# amper.net
KiCad netlist of a schematic drawn in EAGLE
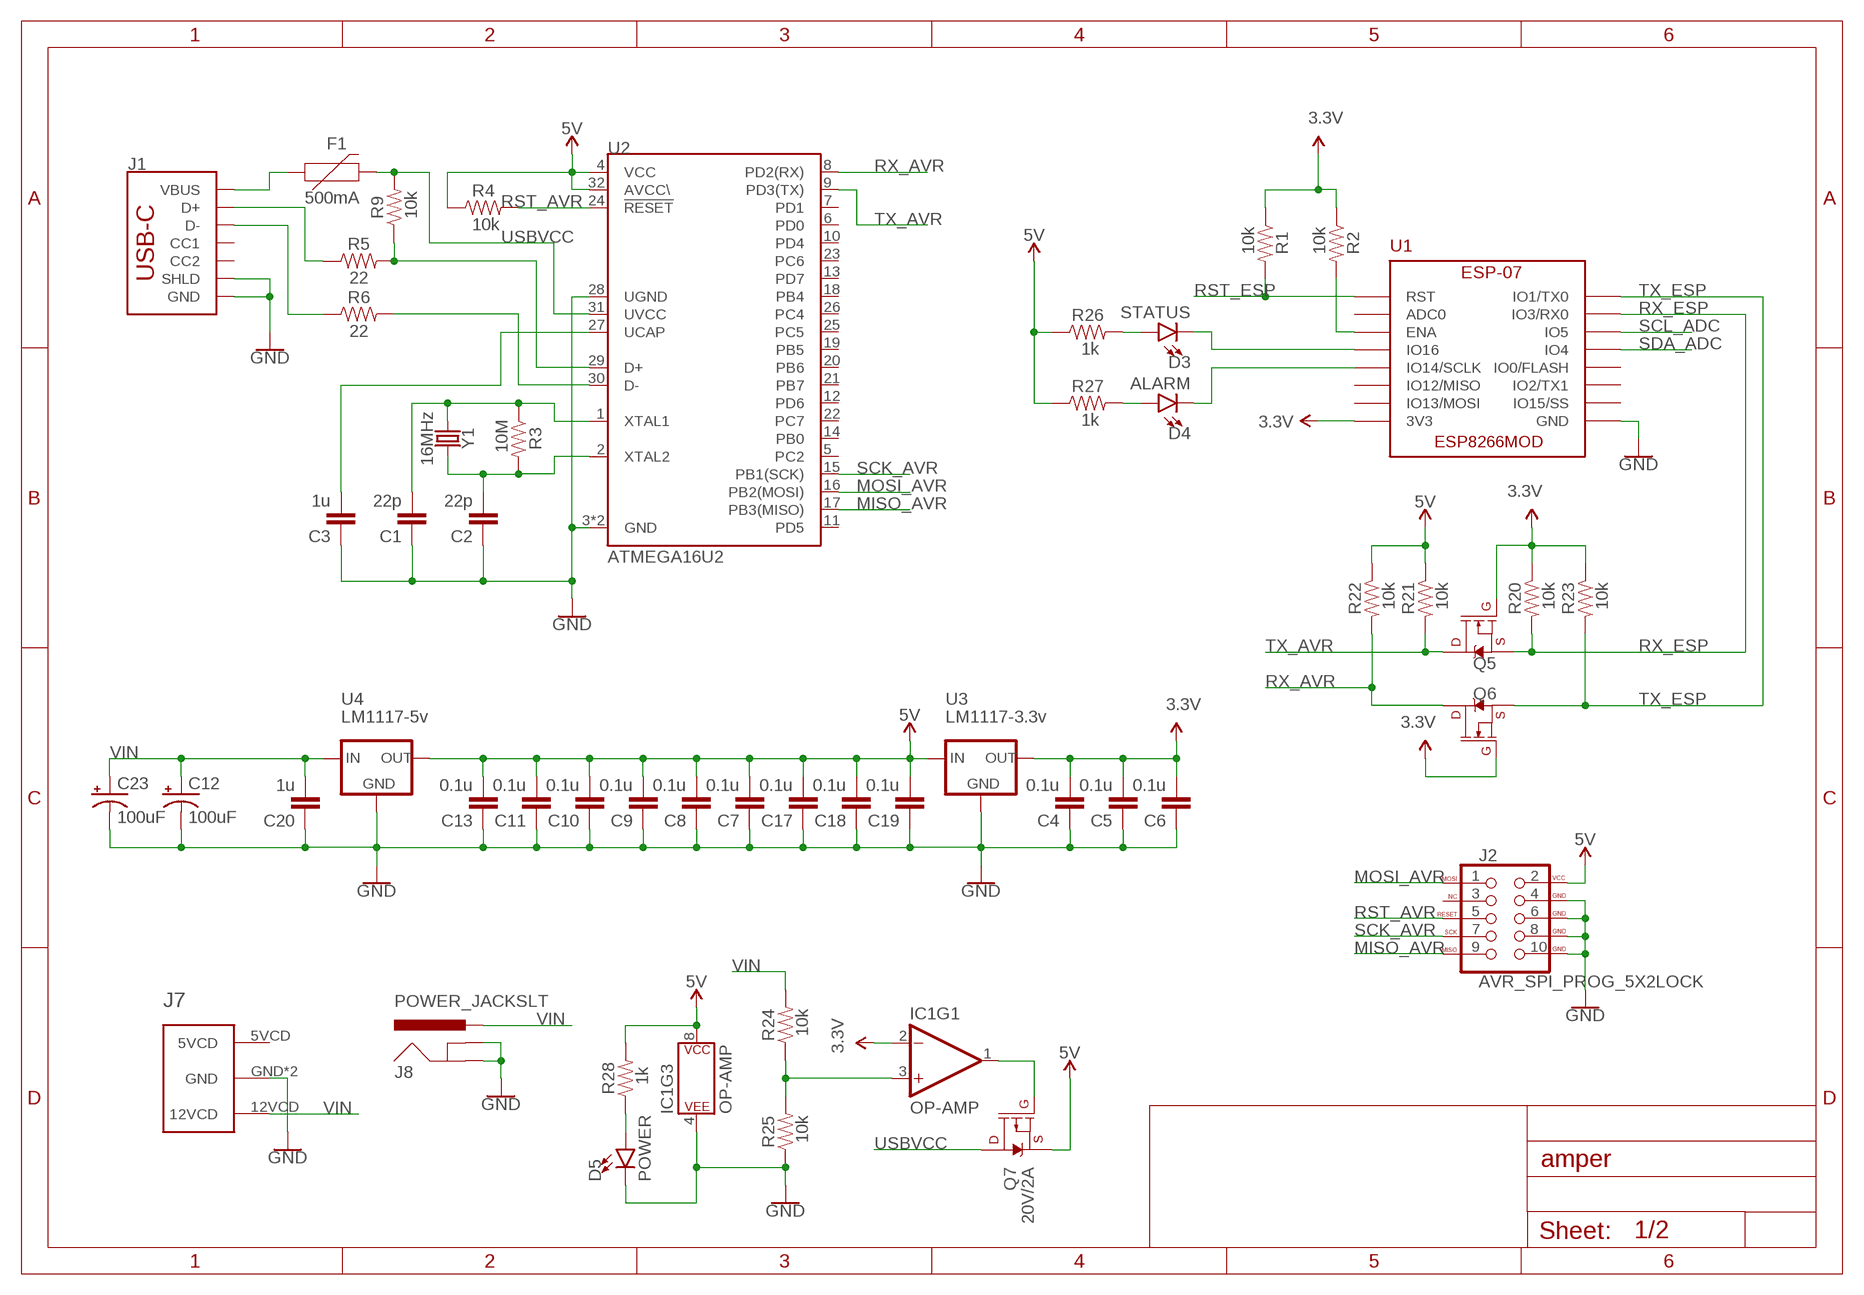
[diagram p0: schematic, sheet 1]
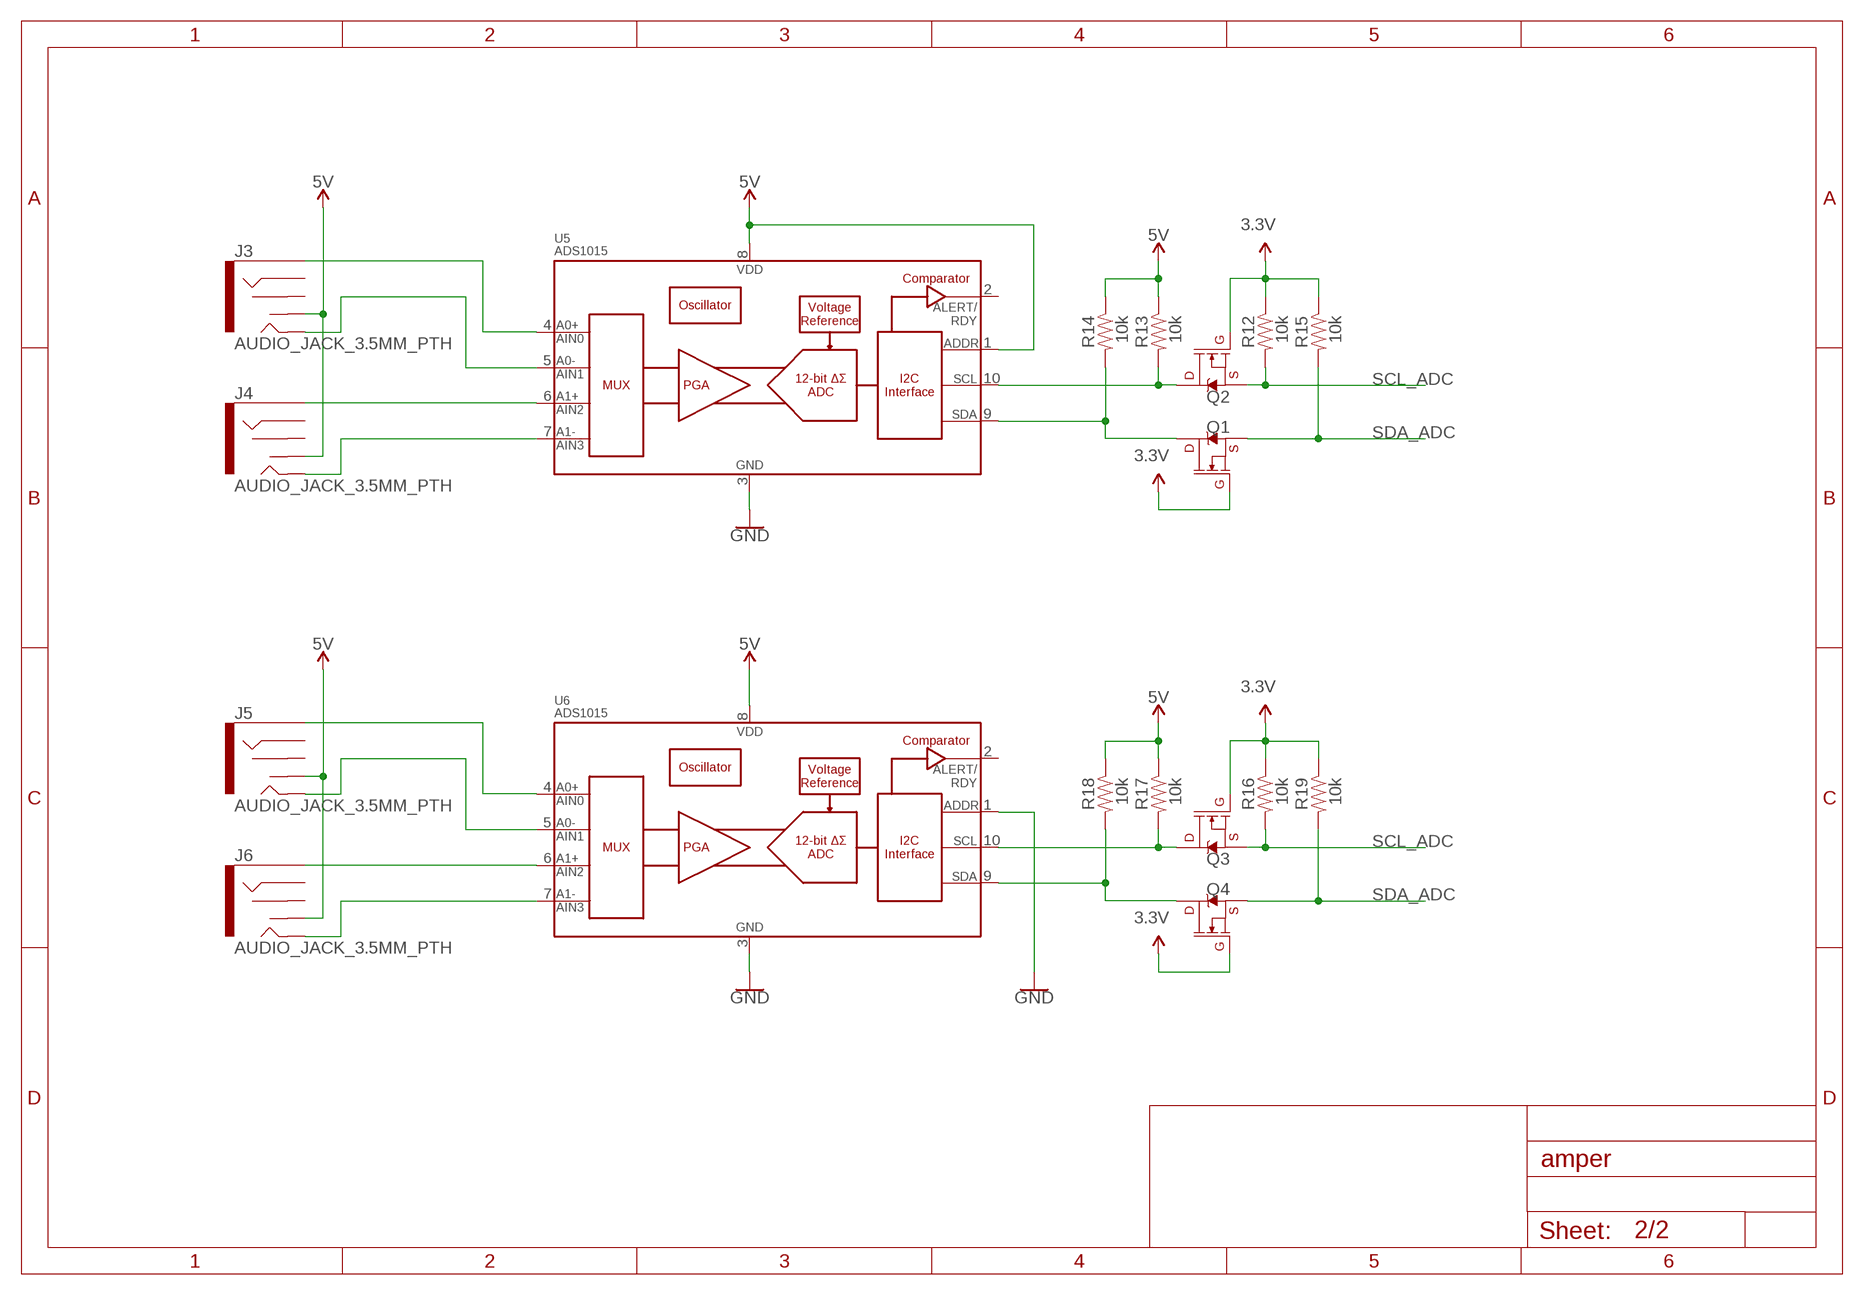
[diagram p1: schematic, sheet 2]

(export (version "E")
  (design (tool "Eeschema 10.0.6"))
  (components
    (comp (ref "J3")
      (value "AUDIO_JACK_3.5MM_PTH")
      (footprint "eagle-import:AUDIO-JACK")
      (libsource (lib "eagle-import") (part "AUDIO_JACK_3.5MM_PTH"))
    )
    (comp (ref "J4")
      (value "AUDIO_JACK_3.5MM_PTH")
      (footprint "eagle-import:AUDIO-JACK")
      (libsource (lib "eagle-import") (part "AUDIO_JACK_3.5MM_PTH"))
    )
    (comp (ref "J5")
      (value "AUDIO_JACK_3.5MM_PTH")
      (footprint "eagle-import:AUDIO-JACK")
      (libsource (lib "eagle-import") (part "AUDIO_JACK_3.5MM_PTH"))
    )
    (comp (ref "J6")
      (value "AUDIO_JACK_3.5MM_PTH")
      (footprint "eagle-import:AUDIO-JACK")
      (libsource (lib "eagle-import") (part "AUDIO_JACK_3.5MM_PTH"))
    )
    (comp (ref "Q1")
      (value "220mA/50V/3.5Ω")
      (footprint "eagle-import:SOT23-3")
      (libsource (lib "eagle-import") (part "MOSFET-NCH-BSS138"))
    )
    (comp (ref "Q2")
      (value "220mA/50V/3.5Ω")
      (footprint "eagle-import:SOT23-3")
      (libsource (lib "eagle-import") (part "MOSFET-NCH-BSS138"))
    )
    (comp (ref "Q3")
      (value "220mA/50V/3.5Ω")
      (footprint "eagle-import:SOT23-3")
      (libsource (lib "eagle-import") (part "MOSFET-NCH-BSS138"))
    )
    (comp (ref "Q4")
      (value "220mA/50V/3.5Ω")
      (footprint "eagle-import:SOT23-3")
      (libsource (lib "eagle-import") (part "MOSFET-NCH-BSS138"))
    )
    (comp (ref "R12")
      (value "10k")
      (footprint "eagle-import:0805")
      (libsource (lib "eagle-import") (part "RESISTOR0805"))
    )
    (comp (ref "R13")
      (value "10k")
      (footprint "eagle-import:0805")
      (libsource (lib "eagle-import") (part "RESISTOR0805"))
    )
    (comp (ref "R14")
      (value "10k")
      (footprint "eagle-import:0805")
      (libsource (lib "eagle-import") (part "RESISTOR0805"))
    )
    (comp (ref "R15")
      (value "10k")
      (footprint "eagle-import:0805")
      (libsource (lib "eagle-import") (part "RESISTOR0805"))
    )
    (comp (ref "R16")
      (value "10k")
      (footprint "eagle-import:0805")
      (libsource (lib "eagle-import") (part "RESISTOR0805"))
    )
    (comp (ref "R17")
      (value "10k")
      (footprint "eagle-import:0805")
      (libsource (lib "eagle-import") (part "RESISTOR0805"))
    )
    (comp (ref "R18")
      (value "10k")
      (footprint "eagle-import:0805")
      (libsource (lib "eagle-import") (part "RESISTOR0805"))
    )
    (comp (ref "R19")
      (value "10k")
      (footprint "eagle-import:0805")
      (libsource (lib "eagle-import") (part "RESISTOR0805"))
    )
    (comp (ref "U5")
      (value "ADS1015")
      (footprint "eagle-import:MSOP10")
      (libsource (lib "eagle-import") (part "ADS1015"))
    )
    (comp (ref "U6")
      (value "ADS1015")
      (footprint "eagle-import:MSOP10")
      (libsource (lib "eagle-import") (part "ADS1015"))
    )
    (comp (ref "C1")
      (value "22p")
      (footprint "eagle-import:0805")
      (libsource (lib "eagle-import") (part "CAP-0805"))
    )
    (comp (ref "C2")
      (value "22p")
      (footprint "eagle-import:0805")
      (libsource (lib "eagle-import") (part "CAP-0805"))
    )
    (comp (ref "C3")
      (value "1u")
      (footprint "eagle-import:0805")
      (libsource (lib "eagle-import") (part "CAP-0805"))
    )
    (comp (ref "C4")
      (value "0.1u")
      (footprint "eagle-import:0805")
      (libsource (lib "eagle-import") (part "CAP-0805"))
    )
    (comp (ref "C5")
      (value "0.1u")
      (footprint "eagle-import:0805")
      (libsource (lib "eagle-import") (part "CAP-0805"))
    )
    (comp (ref "C6")
      (value "0.1u")
      (footprint "eagle-import:0805")
      (libsource (lib "eagle-import") (part "CAP-0805"))
    )
    (comp (ref "C7")
      (value "0.1u")
      (footprint "eagle-import:0805")
      (libsource (lib "eagle-import") (part "CAP-0805"))
    )
    (comp (ref "C8")
      (value "0.1u")
      (footprint "eagle-import:0805")
      (libsource (lib "eagle-import") (part "CAP-0805"))
    )
    (comp (ref "C9")
      (value "0.1u")
      (footprint "eagle-import:0805")
      (libsource (lib "eagle-import") (part "CAP-0805"))
    )
    (comp (ref "C10")
      (value "0.1u")
      (footprint "eagle-import:0805")
      (libsource (lib "eagle-import") (part "CAP-0805"))
    )
    (comp (ref "C11")
      (value "0.1u")
      (footprint "eagle-import:0805")
      (libsource (lib "eagle-import") (part "CAP-0805"))
    )
    (comp (ref "C12")
      (value "100uF")
      (footprint "eagle-import:PANASONIC_D")
      (libsource (lib "eagle-import") (part "100UF-POLAR-25V-20%(ELEC)"))
    )
    (comp (ref "C13")
      (value "0.1u")
      (footprint "eagle-import:0805")
      (libsource (lib "eagle-import") (part "CAP-0805"))
    )
    (comp (ref "C17")
      (value "0.1u")
      (footprint "eagle-import:0805")
      (libsource (lib "eagle-import") (part "CAP-0805"))
    )
    (comp (ref "C18")
      (value "0.1u")
      (footprint "eagle-import:0805")
      (libsource (lib "eagle-import") (part "CAP-0805"))
    )
    (comp (ref "C19")
      (value "0.1u")
      (footprint "eagle-import:0805")
      (libsource (lib "eagle-import") (part "CAP-0805"))
    )
    (comp (ref "C20")
      (value "1u")
      (footprint "eagle-import:0805")
      (libsource (lib "eagle-import") (part "CAP-0805"))
    )
    (comp (ref "C23")
      (value "100uF")
      (footprint "eagle-import:PANASONIC_D")
      (libsource (lib "eagle-import") (part "100UF-POLAR-25V-20%(ELEC)"))
    )
    (comp (ref "D3")
      (value "STATUS")
      (footprint "eagle-import:LED-0603")
      (libsource (lib "eagle-import") (part "LED-YELLOW0603"))
    )
    (comp (ref "D4")
      (value "ALARM")
      (footprint "eagle-import:LED-0603")
      (libsource (lib "eagle-import") (part "LED-YELLOW0603"))
    )
    (comp (ref "D5")
      (value "POWER")
      (footprint "eagle-import:LED-0603")
      (libsource (lib "eagle-import") (part "LED-YELLOW0603"))
    )
    (comp (ref "F1")
      (value "500mA")
      (footprint "eagle-import:1812")
      (libsource (lib "eagle-import") (part "PPTC_16V_2.5A"))
    )
    (comp (ref "IC1")
      (value "OP-AMP")
      (footprint "eagle-import:SO08")
      (libsource (lib "eagle-import") (part "OPAMP-DUALU"))
    )
    (comp (ref "J1")
      (value "USB_C_2-LAYER_PADS")
      (footprint "eagle-import:USB-C-16P-2LAYER-PADS")
      (libsource (lib "eagle-import") (part "USB_C_2-LAYER_PADS"))
    )
    (comp (ref "J2")
      (value "AVR_SPI_PROG_5X2LOCK")
      (footprint "eagle-import:2X5-SHROUDED_LOCK")
      (libsource (lib "eagle-import") (part "AVR_SPI_PROG_5X2LOCK"))
    )
    (comp (ref "J7")
      (value "MOLEX-CPU-POWER")
      (footprint "eagle-import:MOLEX-5.08-4PIN")
      (libsource (lib "eagle-import") (part "MOLEX-CPU-POWER"))
    )
    (comp (ref "J8")
      (value "POWER_JACKSLT")
      (footprint "eagle-import:POWER_JACK_SLOT")
      (libsource (lib "eagle-import") (part "POWER_JACKSLT"))
    )
    (comp (ref "Q5")
      (value "220mA/50V/3.5Ω")
      (footprint "eagle-import:SOT23-3")
      (libsource (lib "eagle-import") (part "MOSFET-NCH-BSS138"))
    )
    (comp (ref "Q6")
      (value "220mA/50V/3.5Ω")
      (footprint "eagle-import:SOT23-3")
      (libsource (lib "eagle-import") (part "MOSFET-NCH-BSS138"))
    )
    (comp (ref "Q7")
      (value "20V/2A")
      (footprint "eagle-import:SOT23-3")
      (libsource (lib "eagle-import") (part "MOSFET_PCH-DMG2305UX-7"))
    )
    (comp (ref "R1")
      (value "10k")
      (footprint "eagle-import:0805")
      (libsource (lib "eagle-import") (part "RESISTOR0805"))
    )
    (comp (ref "R2")
      (value "10k")
      (footprint "eagle-import:0805")
      (libsource (lib "eagle-import") (part "RESISTOR0805"))
    )
    (comp (ref "R3")
      (value "10M")
      (footprint "eagle-import:0805")
      (libsource (lib "eagle-import") (part "RESISTOR0805"))
    )
    (comp (ref "R4")
      (value "10k")
      (footprint "eagle-import:0805")
      (libsource (lib "eagle-import") (part "RESISTOR0805"))
    )
    (comp (ref "R5")
      (value "22")
      (footprint "eagle-import:0805")
      (libsource (lib "eagle-import") (part "RESISTOR0805"))
    )
    (comp (ref "R6")
      (value "22")
      (footprint "eagle-import:0805")
      (libsource (lib "eagle-import") (part "RESISTOR0805"))
    )
    (comp (ref "R9")
      (value "10k")
      (footprint "eagle-import:0805")
      (libsource (lib "eagle-import") (part "RESISTOR0805"))
    )
    (comp (ref "R20")
      (value "10k")
      (footprint "eagle-import:0805")
      (libsource (lib "eagle-import") (part "RESISTOR0805"))
    )
    (comp (ref "R21")
      (value "10k")
      (footprint "eagle-import:0805")
      (libsource (lib "eagle-import") (part "RESISTOR0805"))
    )
    (comp (ref "R22")
      (value "10k")
      (footprint "eagle-import:0805")
      (libsource (lib "eagle-import") (part "RESISTOR0805"))
    )
    (comp (ref "R23")
      (value "10k")
      (footprint "eagle-import:0805")
      (libsource (lib "eagle-import") (part "RESISTOR0805"))
    )
    (comp (ref "R24")
      (value "10k")
      (footprint "eagle-import:0805")
      (libsource (lib "eagle-import") (part "RESISTOR0805"))
    )
    (comp (ref "R25")
      (value "10k")
      (footprint "eagle-import:0805")
      (libsource (lib "eagle-import") (part "RESISTOR0805"))
    )
    (comp (ref "R26")
      (value "1k")
      (footprint "eagle-import:0805")
      (libsource (lib "eagle-import") (part "RESISTOR0805"))
    )
    (comp (ref "R27")
      (value "1k")
      (footprint "eagle-import:0805")
      (libsource (lib "eagle-import") (part "RESISTOR0805"))
    )
    (comp (ref "R28")
      (value "1k")
      (footprint "eagle-import:0805")
      (libsource (lib "eagle-import") (part "RESISTOR0805"))
    )
    (comp (ref "U1")
      (value "ESP-07")
      (footprint "eagle-import:ESP-07")
      (libsource (lib "eagle-import") (part "ESP-07"))
    )
    (comp (ref "U2")
      (value "ATMEGA16U2")
      (footprint "eagle-import:QFN32")
      (libsource (lib "eagle-import") (part "ATMEGA16U2"))
    )
    (comp (ref "U3")
      (value "LM1117-3.3v")
      (footprint "eagle-import:SOT223")
      (libsource (lib "eagle-import") (part "V_REG_LD1117VXXLD1117-SMD"))
    )
    (comp (ref "U4")
      (value "LM1117-5v")
      (footprint "eagle-import:SOT223")
      (libsource (lib "eagle-import") (part "V_REG_LD1117VXXLD1117-SMD"))
    )
    (comp (ref "Y1")
      (value "16MHz")
      (footprint "eagle-import:CRYSTAL-SMD-5X3.2-4PAD")
      (libsource (lib "eagle-import") (part "CRYSTAL-16MHZSMD-5X3.2"))
    )
  )
  (nets
    (net (code "1") (name "3.3V") (class "Default")
      (node (ref "C4") (pin "2") (pinfunction "2_2") (pintype "passive"))
      (node (ref "C5") (pin "2") (pinfunction "2_2") (pintype "passive"))
      (node (ref "C6") (pin "2") (pinfunction "2_2") (pintype "passive"))
      (node (ref "IC1") (pin "2") (pinfunction "-IN_2") (pintype "input"))
      (node (ref "Q1") (pin "1") (pinfunction "G_1") (pintype "bidirectional"))
      (node (ref "Q2") (pin "1") (pinfunction "G_1") (pintype "bidirectional"))
      (node (ref "Q3") (pin "1") (pinfunction "G_1") (pintype "bidirectional"))
      (node (ref "Q4") (pin "1") (pinfunction "G_1") (pintype "bidirectional"))
      (node (ref "Q5") (pin "1") (pinfunction "G_1") (pintype "bidirectional"))
      (node (ref "Q6") (pin "1") (pinfunction "G_1") (pintype "bidirectional"))
      (node (ref "R1") (pin "1") (pinfunction "1_1") (pintype "passive"))
      (node (ref "R12") (pin "1") (pinfunction "1_1") (pintype "passive"))
      (node (ref "R15") (pin "1") (pinfunction "1_1") (pintype "passive"))
      (node (ref "R16") (pin "1") (pinfunction "1_1") (pintype "passive"))
      (node (ref "R19") (pin "1") (pinfunction "1_1") (pintype "passive"))
      (node (ref "R2") (pin "1") (pinfunction "1_1") (pintype "passive"))
      (node (ref "R20") (pin "1") (pinfunction "1_1") (pintype "passive"))
      (node (ref "R23") (pin "1") (pinfunction "1_1") (pintype "passive"))
      (node (ref "U1") (pin "3V3") (pinfunction "3V3_3V3") (pintype "power_in"))
      (node (ref "U3") (pin "2") (pinfunction "OUT_2") (pintype "passive"))
    )
    (net (code "2") (name "5V") (class "Default")
      (node (ref "C10") (pin "2") (pinfunction "2_2") (pintype "passive"))
      (node (ref "C11") (pin "2") (pinfunction "2_2") (pintype "passive"))
      (node (ref "C13") (pin "2") (pinfunction "2_2") (pintype "passive"))
      (node (ref "C17") (pin "2") (pinfunction "2_2") (pintype "passive"))
      (node (ref "C18") (pin "2") (pinfunction "2_2") (pintype "passive"))
      (node (ref "C19") (pin "2") (pinfunction "2_2") (pintype "passive"))
      (node (ref "C7") (pin "2") (pinfunction "2_2") (pintype "passive"))
      (node (ref "C8") (pin "2") (pinfunction "2_2") (pintype "passive"))
      (node (ref "C9") (pin "2") (pinfunction "2_2") (pintype "passive"))
      (node (ref "IC1") (pin "8") (pinfunction "P$V+_8") (pintype "bidirectional"))
      (node (ref "J2") (pin "2") (pinfunction "VCC_2") (pintype "power_in"))
      (node (ref "J3") (pin "TSH") (pinfunction "TSH_TSH") (pintype "bidirectional"))
      (node (ref "J4") (pin "TSH") (pinfunction "TSH_TSH") (pintype "bidirectional"))
      (node (ref "J5") (pin "TSH") (pinfunction "TSH_TSH") (pintype "bidirectional"))
      (node (ref "J6") (pin "TSH") (pinfunction "TSH_TSH") (pintype "bidirectional"))
      (node (ref "Q7") (pin "2") (pinfunction "S_2") (pintype "bidirectional"))
      (node (ref "R13") (pin "1") (pinfunction "1_1") (pintype "passive"))
      (node (ref "R14") (pin "1") (pinfunction "1_1") (pintype "passive"))
      (node (ref "R17") (pin "1") (pinfunction "1_1") (pintype "passive"))
      (node (ref "R18") (pin "1") (pinfunction "1_1") (pintype "passive"))
      (node (ref "R21") (pin "1") (pinfunction "1_1") (pintype "passive"))
      (node (ref "R22") (pin "1") (pinfunction "1_1") (pintype "passive"))
      (node (ref "R26") (pin "1") (pinfunction "1_1") (pintype "passive"))
      (node (ref "R27") (pin "1") (pinfunction "1_1") (pintype "passive"))
      (node (ref "R28") (pin "2") (pinfunction "2_2") (pintype "passive"))
      (node (ref "R4") (pin "1") (pinfunction "1_1") (pintype "passive"))
      (node (ref "U2") (pin "32") (pinfunction "AVCC\\_32") (pintype "bidirectional"))
      (node (ref "U2") (pin "4") (pinfunction "VCC_4") (pintype "bidirectional"))
      (node (ref "U3") (pin "3") (pinfunction "IN_3") (pintype "input"))
      (node (ref "U4") (pin "2") (pinfunction "OUT_2") (pintype "passive"))
      (node (ref "U5") (pin "1") (pinfunction "ADDR_1") (pintype "bidirectional"))
      (node (ref "U5") (pin "8") (pinfunction "VDD_8") (pintype "bidirectional"))
      (node (ref "U6") (pin "8") (pinfunction "VDD_8") (pintype "bidirectional"))
    )
    (net (code "3") (name "GND") (class "Default")
      (node (ref "C1") (pin "1") (pinfunction "1_1") (pintype "passive"))
      (node (ref "C10") (pin "1") (pinfunction "1_1") (pintype "passive"))
      (node (ref "C11") (pin "1") (pinfunction "1_1") (pintype "passive"))
      (node (ref "C12") (pin "-") (pinfunction "-_-") (pintype "passive"))
      (node (ref "C13") (pin "1") (pinfunction "1_1") (pintype "passive"))
      (node (ref "C17") (pin "1") (pinfunction "1_1") (pintype "passive"))
      (node (ref "C18") (pin "1") (pinfunction "1_1") (pintype "passive"))
      (node (ref "C19") (pin "1") (pinfunction "1_1") (pintype "passive"))
      (node (ref "C2") (pin "1") (pinfunction "1_1") (pintype "passive"))
      (node (ref "C20") (pin "1") (pinfunction "1_1") (pintype "passive"))
      (node (ref "C23") (pin "-") (pinfunction "-_-") (pintype "passive"))
      (node (ref "C3") (pin "1") (pinfunction "1_1") (pintype "passive"))
      (node (ref "C4") (pin "1") (pinfunction "1_1") (pintype "passive"))
      (node (ref "C5") (pin "1") (pinfunction "1_1") (pintype "passive"))
      (node (ref "C6") (pin "1") (pinfunction "1_1") (pintype "passive"))
      (node (ref "C7") (pin "1") (pinfunction "1_1") (pintype "passive"))
      (node (ref "C8") (pin "1") (pinfunction "1_1") (pintype "passive"))
      (node (ref "C9") (pin "1") (pinfunction "1_1") (pintype "passive"))
      (node (ref "D5") (pin "C") (pinfunction "C_C") (pintype "passive"))
      (node (ref "IC1") (pin "4") (pinfunction "P$V-_4") (pintype "bidirectional"))
      (node (ref "J1") (pin "GND") (pinfunction "GND_GND") (pintype "bidirectional"))
      (node (ref "J1") (pin "GND2") (pinfunction "GND_GND2") (pintype "bidirectional"))
      (node (ref "J1") (pin "SHLD1") (pinfunction "SHLD_SHLD1") (pintype "bidirectional"))
      (node (ref "J1") (pin "SHLD2") (pinfunction "SHLD_SHLD2") (pintype "bidirectional"))
      (node (ref "J1") (pin "SHLD3") (pinfunction "SHLD_SHLD3") (pintype "bidirectional"))
      (node (ref "J1") (pin "SHLD4") (pinfunction "SHLD_SHLD4") (pintype "bidirectional"))
      (node (ref "J2") (pin "10") (pinfunction "GND_10") (pintype "power_in"))
      (node (ref "J2") (pin "4") (pinfunction "GND_4") (pintype "power_in"))
      (node (ref "J2") (pin "6") (pinfunction "GND_6") (pintype "power_in"))
      (node (ref "J2") (pin "8") (pinfunction "GND_8") (pintype "power_in"))
      (node (ref "J7") (pin "GND") (pinfunction "GND_GND") (pintype "bidirectional"))
      (node (ref "J7") (pin "GND2") (pinfunction "GND_GND2") (pintype "bidirectional"))
      (node (ref "J8") (pin "GND@1") (pinfunction "GNDBREAK_GND@1") (pintype "bidirectional"))
      (node (ref "J8") (pin "GND@2") (pinfunction "GND_GND@2") (pintype "bidirectional"))
      (node (ref "R25") (pin "1") (pinfunction "1_1") (pintype "passive"))
      (node (ref "U1") (pin "GND") (pinfunction "GND_GND") (pintype "power_in"))
      (node (ref "U2") (pin "28") (pinfunction "UGND_28") (pintype "bidirectional"))
      (node (ref "U2") (pin "3") (pinfunction "GND_3") (pintype "bidirectional"))
      (node (ref "U2") (pin "EP") (pinfunction "GND_EP") (pintype "bidirectional"))
      (node (ref "U3") (pin "1") (pinfunction "GND_1") (pintype "input"))
      (node (ref "U4") (pin "1") (pinfunction "GND_1") (pintype "input"))
      (node (ref "U5") (pin "3") (pinfunction "VSS_3") (pintype "bidirectional"))
      (node (ref "U6") (pin "1") (pinfunction "ADDR_1") (pintype "bidirectional"))
      (node (ref "U6") (pin "3") (pinfunction "VSS_3") (pintype "bidirectional"))
    )
    (net (code "4") (name "MISO_AVR") (class "Default")
      (node (ref "J2") (pin "9") (pinfunction "MISO_9") (pintype "passive"))
      (node (ref "U2") (pin "17") (pinfunction "PB3(MISO)_17") (pintype "bidirectional"))
    )
    (net (code "5") (name "MOSI_AVR") (class "Default")
      (node (ref "J2") (pin "1") (pinfunction "MOSI_1") (pintype "passive"))
      (node (ref "U2") (pin "16") (pinfunction "PB2(MOSI)_16") (pintype "bidirectional"))
    )
    (net (code "6") (name "Net-(D3-PadA)") (class "Default")
      (node (ref "D3") (pin "A") (pinfunction "A_A") (pintype "passive"))
      (node (ref "R26") (pin "2") (pinfunction "2_2") (pintype "passive"))
    )
    (net (code "7") (name "Net-(D4-PadA)") (class "Default")
      (node (ref "D4") (pin "A") (pinfunction "A_A") (pintype "passive"))
      (node (ref "R27") (pin "2") (pinfunction "2_2") (pintype "passive"))
    )
    (net (code "8") (name "Net-(D5-PadA)") (class "Default")
      (node (ref "D5") (pin "A") (pinfunction "A_A") (pintype "passive"))
      (node (ref "R28") (pin "1") (pinfunction "1_1") (pintype "passive"))
    )
    (net (code "9") (name "Net-(F1-Pad1)") (class "Default")
      (node (ref "F1") (pin "1") (pinfunction "1_1") (pintype "bidirectional"))
      (node (ref "J1") (pin "VBUS1") (pinfunction "VBUS_VBUS1") (pintype "bidirectional"))
      (node (ref "J1") (pin "VBUS2") (pinfunction "VBUS_VBUS2") (pintype "bidirectional"))
    )
    (net (code "10") (name "Net-(IC1A-+IN)") (class "Default")
      (node (ref "IC1") (pin "3") (pinfunction "+IN_3") (pintype "input"))
      (node (ref "R24") (pin "1") (pinfunction "1_1") (pintype "passive"))
      (node (ref "R25") (pin "2") (pinfunction "2_2") (pintype "passive"))
    )
    (net (code "11") (name "Net-(IC1A-OUT)") (class "Default")
      (node (ref "IC1") (pin "1") (pinfunction "OUT_1") (pintype "output"))
      (node (ref "Q7") (pin "1") (pinfunction "G_1") (pintype "bidirectional"))
    )
    (net (code "12") (name "Net-(J1-D+-PadA6)") (class "Default")
      (node (ref "J1") (pin "A6") (pinfunction "D+_A6") (pintype "bidirectional"))
      (node (ref "J1") (pin "B6") (pinfunction "D+_B6") (pintype "bidirectional"))
      (node (ref "R5") (pin "1") (pinfunction "1_1") (pintype "passive"))
    )
    (net (code "13") (name "Net-(J1-D--PadA7)") (class "Default")
      (node (ref "J1") (pin "A7") (pinfunction "D-_A7") (pintype "bidirectional"))
      (node (ref "J1") (pin "B7") (pinfunction "D-_B7") (pintype "bidirectional"))
      (node (ref "R6") (pin "1") (pinfunction "1_1") (pintype "passive"))
    )
    (net (code "14") (name "Net-(Q1-D)") (class "Default")
      (node (ref "Q1") (pin "3") (pinfunction "D_3") (pintype "bidirectional"))
      (node (ref "R14") (pin "2") (pinfunction "2_2") (pintype "passive"))
      (node (ref "U5") (pin "9") (pinfunction "SDA_9") (pintype "bidirectional"))
    )
    (net (code "15") (name "Net-(Q2-D)") (class "Default")
      (node (ref "Q2") (pin "3") (pinfunction "D_3") (pintype "bidirectional"))
      (node (ref "R13") (pin "2") (pinfunction "2_2") (pintype "passive"))
      (node (ref "U5") (pin "10") (pinfunction "SCL_10") (pintype "bidirectional"))
    )
    (net (code "16") (name "Net-(Q3-D)") (class "Default")
      (node (ref "Q3") (pin "3") (pinfunction "D_3") (pintype "bidirectional"))
      (node (ref "R17") (pin "2") (pinfunction "2_2") (pintype "passive"))
      (node (ref "U6") (pin "10") (pinfunction "SCL_10") (pintype "bidirectional"))
    )
    (net (code "17") (name "Net-(Q4-D)") (class "Default")
      (node (ref "Q4") (pin "3") (pinfunction "D_3") (pintype "bidirectional"))
      (node (ref "R18") (pin "2") (pinfunction "2_2") (pintype "passive"))
      (node (ref "U6") (pin "9") (pinfunction "SDA_9") (pintype "bidirectional"))
    )
    (net (code "18") (name "Net-(R2-Pad2)") (class "Default")
      (node (ref "R2") (pin "2") (pinfunction "2_2") (pintype "passive"))
      (node (ref "U1") (pin "ENA") (pinfunction "ENA_ENA") (pintype "input"))
    )
    (net (code "19") (name "Net-(U1-IO14{slash}SCLK)") (class "Default")
      (node (ref "D4") (pin "C") (pinfunction "C_C") (pintype "passive"))
      (node (ref "U1") (pin "IO14") (pinfunction "IO14/SCLK_IO14") (pintype "bidirectional"))
    )
    (net (code "20") (name "Net-(U1-IO16)") (class "Default")
      (node (ref "D3") (pin "C") (pinfunction "C_C") (pintype "passive"))
      (node (ref "U1") (pin "I016") (pinfunction "IO16_I016") (pintype "bidirectional"))
    )
    (net (code "21") (name "Net-(U2-D+)") (class "Default")
      (node (ref "R5") (pin "2") (pinfunction "2_2") (pintype "passive"))
      (node (ref "R9") (pin "1") (pinfunction "1_1") (pintype "passive"))
      (node (ref "U2") (pin "29") (pinfunction "D+_29") (pintype "bidirectional"))
    )
    (net (code "22") (name "Net-(U2-D-)") (class "Default")
      (node (ref "R6") (pin "2") (pinfunction "2_2") (pintype "passive"))
      (node (ref "U2") (pin "30") (pinfunction "D-_30") (pintype "bidirectional"))
    )
    (net (code "23") (name "Net-(U2-UCAP)") (class "Default")
      (node (ref "C3") (pin "2") (pinfunction "2_2") (pintype "passive"))
      (node (ref "U2") (pin "27") (pinfunction "UCAP_27") (pintype "bidirectional"))
    )
    (net (code "24") (name "Net-(U2-XTAL1)") (class "Default")
      (node (ref "C1") (pin "2") (pinfunction "2_2") (pintype "passive"))
      (node (ref "R3") (pin "1") (pinfunction "1_1") (pintype "passive"))
      (node (ref "U2") (pin "1") (pinfunction "XTAL1_1") (pintype "bidirectional"))
      (node (ref "Y1") (pin "1") (pinfunction "1_1") (pintype "passive"))
    )
    (net (code "25") (name "Net-(U2-XTAL2)") (class "Default")
      (node (ref "C2") (pin "2") (pinfunction "2_2") (pintype "passive"))
      (node (ref "R3") (pin "2") (pinfunction "2_2") (pintype "passive"))
      (node (ref "U2") (pin "2") (pinfunction "XTAL2_2") (pintype "bidirectional"))
      (node (ref "Y1") (pin "3") (pinfunction "2_3") (pintype "passive"))
    )
    (net (code "26") (name "Net-(U5-AIN0)") (class "Default")
      (node (ref "J3") (pin "SLEEVE") (pinfunction "SLEEVE_SLEEVE") (pintype "bidirectional"))
      (node (ref "U5") (pin "4") (pinfunction "AIN0_4") (pintype "bidirectional"))
    )
    (net (code "27") (name "Net-(U5-AIN1)") (class "Default")
      (node (ref "J3") (pin "TIP") (pinfunction "TIP_TIP") (pintype "bidirectional"))
      (node (ref "U5") (pin "5") (pinfunction "AIN1_5") (pintype "bidirectional"))
    )
    (net (code "28") (name "Net-(U5-AIN2)") (class "Default")
      (node (ref "J4") (pin "SLEEVE") (pinfunction "SLEEVE_SLEEVE") (pintype "bidirectional"))
      (node (ref "U5") (pin "6") (pinfunction "AIN2_6") (pintype "bidirectional"))
    )
    (net (code "29") (name "Net-(U5-AIN3)") (class "Default")
      (node (ref "J4") (pin "TIP") (pinfunction "TIP_TIP") (pintype "bidirectional"))
      (node (ref "U5") (pin "7") (pinfunction "AIN3_7") (pintype "bidirectional"))
    )
    (net (code "30") (name "Net-(U6-AIN0)") (class "Default")
      (node (ref "J5") (pin "SLEEVE") (pinfunction "SLEEVE_SLEEVE") (pintype "bidirectional"))
      (node (ref "U6") (pin "4") (pinfunction "AIN0_4") (pintype "bidirectional"))
    )
    (net (code "31") (name "Net-(U6-AIN1)") (class "Default")
      (node (ref "J5") (pin "TIP") (pinfunction "TIP_TIP") (pintype "bidirectional"))
      (node (ref "U6") (pin "5") (pinfunction "AIN1_5") (pintype "bidirectional"))
    )
    (net (code "32") (name "Net-(U6-AIN2)") (class "Default")
      (node (ref "J6") (pin "SLEEVE") (pinfunction "SLEEVE_SLEEVE") (pintype "bidirectional"))
      (node (ref "U6") (pin "6") (pinfunction "AIN2_6") (pintype "bidirectional"))
    )
    (net (code "33") (name "Net-(U6-AIN3)") (class "Default")
      (node (ref "J6") (pin "TIP") (pinfunction "TIP_TIP") (pintype "bidirectional"))
      (node (ref "U6") (pin "7") (pinfunction "AIN3_7") (pintype "bidirectional"))
    )
    (net (code "34") (name "RST_AVR") (class "Default")
      (node (ref "J2") (pin "5") (pinfunction "RESET_5") (pintype "passive"))
      (node (ref "R4") (pin "2") (pinfunction "2_2") (pintype "passive"))
      (node (ref "U2") (pin "24") (pinfunction "~{RESET}_24") (pintype "bidirectional"))
    )
    (net (code "35") (name "RST_ESP") (class "Default")
      (node (ref "R1") (pin "2") (pinfunction "2_2") (pintype "passive"))
      (node (ref "U1") (pin "RST") (pinfunction "RST_RST") (pintype "input"))
    )
    (net (code "36") (name "RX_AVR") (class "Default")
      (node (ref "Q6") (pin "3") (pinfunction "D_3") (pintype "bidirectional"))
      (node (ref "R22") (pin "2") (pinfunction "2_2") (pintype "passive"))
      (node (ref "U2") (pin "8") (pinfunction "PD2(RX)_8") (pintype "bidirectional"))
    )
    (net (code "37") (name "RX_ESP") (class "Default")
      (node (ref "Q5") (pin "2") (pinfunction "S_2") (pintype "bidirectional"))
      (node (ref "R20") (pin "2") (pinfunction "2_2") (pintype "passive"))
      (node (ref "U1") (pin "RX0") (pinfunction "IO3/RX0_RX0") (pintype "bidirectional"))
    )
    (net (code "38") (name "SCK_AVR") (class "Default")
      (node (ref "J2") (pin "7") (pinfunction "SCK_7") (pintype "passive"))
      (node (ref "U2") (pin "15") (pinfunction "PB1(SCK)_15") (pintype "bidirectional"))
    )
    (net (code "39") (name "SCL_ADC") (class "Default")
      (node (ref "Q2") (pin "2") (pinfunction "S_2") (pintype "bidirectional"))
      (node (ref "Q3") (pin "2") (pinfunction "S_2") (pintype "bidirectional"))
      (node (ref "R12") (pin "2") (pinfunction "2_2") (pintype "passive"))
      (node (ref "R16") (pin "2") (pinfunction "2_2") (pintype "passive"))
      (node (ref "U1") (pin "IO5") (pinfunction "IO5_IO5") (pintype "bidirectional"))
    )
    (net (code "40") (name "SDA_ADC") (class "Default")
      (node (ref "Q1") (pin "2") (pinfunction "S_2") (pintype "bidirectional"))
      (node (ref "Q4") (pin "2") (pinfunction "S_2") (pintype "bidirectional"))
      (node (ref "R15") (pin "2") (pinfunction "2_2") (pintype "passive"))
      (node (ref "R19") (pin "2") (pinfunction "2_2") (pintype "passive"))
      (node (ref "U1") (pin "IO4") (pinfunction "IO4_IO4") (pintype "bidirectional"))
    )
    (net (code "41") (name "TX_AVR") (class "Default")
      (node (ref "Q5") (pin "3") (pinfunction "D_3") (pintype "bidirectional"))
      (node (ref "R21") (pin "2") (pinfunction "2_2") (pintype "passive"))
      (node (ref "U2") (pin "9") (pinfunction "PD3(TX)_9") (pintype "bidirectional"))
    )
    (net (code "42") (name "TX_ESP") (class "Default")
      (node (ref "Q6") (pin "2") (pinfunction "S_2") (pintype "bidirectional"))
      (node (ref "R23") (pin "2") (pinfunction "2_2") (pintype "passive"))
      (node (ref "U1") (pin "TX0") (pinfunction "IO1/TX0_TX0") (pintype "bidirectional"))
    )
    (net (code "43") (name "USBVCC") (class "Default")
      (node (ref "F1") (pin "2") (pinfunction "2_2") (pintype "bidirectional"))
      (node (ref "Q7") (pin "3") (pinfunction "D_3") (pintype "bidirectional"))
      (node (ref "R9") (pin "2") (pinfunction "2_2") (pintype "passive"))
      (node (ref "U2") (pin "31") (pinfunction "UVCC_31") (pintype "bidirectional"))
    )
    (net (code "44") (name "VIN") (class "Default")
      (node (ref "C12") (pin "+") (pinfunction "+_+") (pintype "passive"))
      (node (ref "C20") (pin "2") (pinfunction "2_2") (pintype "passive"))
      (node (ref "C23") (pin "+") (pinfunction "+_+") (pintype "passive"))
      (node (ref "J7") (pin "12VCD") (pinfunction "12VCD_12VCD") (pintype "bidirectional"))
      (node (ref "J8") (pin "PWR") (pinfunction "PWR_PWR") (pintype "bidirectional"))
      (node (ref "R24") (pin "2") (pinfunction "2_2") (pintype "passive"))
      (node (ref "U4") (pin "3") (pinfunction "IN_3") (pintype "input"))
    )
    (net (code "45") (name "unconnected-(J1-CC1-PadA5)") (class "Default")
      (node (ref "J1") (pin "A5") (pinfunction "CC1_A5") (pintype "bidirectional"))
    )
    (net (code "46") (name "unconnected-(J1-CC2-PadB5)") (class "Default")
      (node (ref "J1") (pin "B5") (pinfunction "CC2_B5") (pintype "bidirectional"))
    )
    (net (code "47") (name "unconnected-(J2-NC-Pad3)") (class "Default")
      (node (ref "J2") (pin "3") (pinfunction "NC_3") (pintype "no_connect"))
    )
    (net (code "48") (name "unconnected-(J3-PadRING)") (class "Default")
      (node (ref "J3") (pin "RING") (pinfunction "RING_RING") (pintype "bidirectional"))
    )
    (net (code "49") (name "unconnected-(J3-PadRSH)") (class "Default")
      (node (ref "J3") (pin "RSH") (pinfunction "RSH_RSH") (pintype "bidirectional"))
    )
    (net (code "50") (name "unconnected-(J4-PadRING)") (class "Default")
      (node (ref "J4") (pin "RING") (pinfunction "RING_RING") (pintype "bidirectional"))
    )
    (net (code "51") (name "unconnected-(J4-PadRSH)") (class "Default")
      (node (ref "J4") (pin "RSH") (pinfunction "RSH_RSH") (pintype "bidirectional"))
    )
    (net (code "52") (name "unconnected-(J5-PadRING)") (class "Default")
      (node (ref "J5") (pin "RING") (pinfunction "RING_RING") (pintype "bidirectional"))
    )
    (net (code "53") (name "unconnected-(J5-PadRSH)") (class "Default")
      (node (ref "J5") (pin "RSH") (pinfunction "RSH_RSH") (pintype "bidirectional"))
    )
    (net (code "54") (name "unconnected-(J6-PadRING)") (class "Default")
      (node (ref "J6") (pin "RING") (pinfunction "RING_RING") (pintype "bidirectional"))
    )
    (net (code "55") (name "unconnected-(J6-PadRSH)") (class "Default")
      (node (ref "J6") (pin "RSH") (pinfunction "RSH_RSH") (pintype "bidirectional"))
    )
    (net (code "56") (name "unconnected-(J7-Pad5VCD)") (class "Default")
      (node (ref "J7") (pin "5VCD") (pinfunction "5VCD_5VCD") (pintype "bidirectional"))
    )
    (net (code "57") (name "unconnected-(U1-ADC0-PadADC)") (class "Default")
      (node (ref "U1") (pin "ADC") (pinfunction "ADC0_ADC") (pintype "input"))
    )
    (net (code "58") (name "unconnected-(U1-IO0{slash}FLASH-PadIO0)") (class "Default")
      (node (ref "U1") (pin "IO0") (pinfunction "IO0/FLASH_IO0") (pintype "bidirectional"))
    )
    (net (code "59") (name "unconnected-(U1-IO2{slash}TX1-PadIO2)") (class "Default")
      (node (ref "U1") (pin "IO2") (pinfunction "IO2/TX1_IO2") (pintype "bidirectional"))
    )
    (net (code "60") (name "unconnected-(U1-IO12{slash}MISO-PadIO12)") (class "Default")
      (node (ref "U1") (pin "IO12") (pinfunction "IO12/MISO_IO12") (pintype "bidirectional"))
    )
    (net (code "61") (name "unconnected-(U1-IO13{slash}MOSI-PadIO13)") (class "Default")
      (node (ref "U1") (pin "IO13") (pinfunction "IO13/MOSI_IO13") (pintype "bidirectional"))
    )
    (net (code "62") (name "unconnected-(U1-IO15{slash}SS-PadIO15)") (class "Default")
      (node (ref "U1") (pin "IO15") (pinfunction "IO15/SS_IO15") (pintype "bidirectional"))
    )
    (net (code "63") (name "unconnected-(U2-PB0-Pad14)") (class "Default")
      (node (ref "U2") (pin "14") (pinfunction "PB0_14") (pintype "bidirectional"))
    )
    (net (code "64") (name "unconnected-(U2-PB4-Pad18)") (class "Default")
      (node (ref "U2") (pin "18") (pinfunction "PB4_18") (pintype "bidirectional"))
    )
    (net (code "65") (name "unconnected-(U2-PB5-Pad19)") (class "Default")
      (node (ref "U2") (pin "19") (pinfunction "PB5_19") (pintype "bidirectional"))
    )
    (net (code "66") (name "unconnected-(U2-PB6-Pad20)") (class "Default")
      (node (ref "U2") (pin "20") (pinfunction "PB6_20") (pintype "bidirectional"))
    )
    (net (code "67") (name "unconnected-(U2-PB7-Pad21)") (class "Default")
      (node (ref "U2") (pin "21") (pinfunction "PB7_21") (pintype "bidirectional"))
    )
    (net (code "68") (name "unconnected-(U2-PC2-Pad5)") (class "Default")
      (node (ref "U2") (pin "5") (pinfunction "PC2_5") (pintype "bidirectional"))
    )
    (net (code "69") (name "unconnected-(U2-PC4-Pad26)") (class "Default")
      (node (ref "U2") (pin "26") (pinfunction "PC4_26") (pintype "bidirectional"))
    )
    (net (code "70") (name "unconnected-(U2-PC5-Pad25)") (class "Default")
      (node (ref "U2") (pin "25") (pinfunction "PC5_25") (pintype "bidirectional"))
    )
    (net (code "71") (name "unconnected-(U2-PC6-Pad23)") (class "Default")
      (node (ref "U2") (pin "23") (pinfunction "PC6_23") (pintype "bidirectional"))
    )
    (net (code "72") (name "unconnected-(U2-PC7-Pad22)") (class "Default")
      (node (ref "U2") (pin "22") (pinfunction "PC7_22") (pintype "bidirectional"))
    )
    (net (code "73") (name "unconnected-(U2-PD0-Pad6)") (class "Default")
      (node (ref "U2") (pin "6") (pinfunction "PD0_6") (pintype "bidirectional"))
    )
    (net (code "74") (name "unconnected-(U2-PD1-Pad7)") (class "Default")
      (node (ref "U2") (pin "7") (pinfunction "PD1_7") (pintype "bidirectional"))
    )
    (net (code "75") (name "unconnected-(U2-PD4-Pad10)") (class "Default")
      (node (ref "U2") (pin "10") (pinfunction "PD4_10") (pintype "bidirectional"))
    )
    (net (code "76") (name "unconnected-(U2-PD5-Pad11)") (class "Default")
      (node (ref "U2") (pin "11") (pinfunction "PD5_11") (pintype "bidirectional"))
    )
    (net (code "77") (name "unconnected-(U2-PD6-Pad12)") (class "Default")
      (node (ref "U2") (pin "12") (pinfunction "PD6_12") (pintype "bidirectional"))
    )
    (net (code "78") (name "unconnected-(U2-PD7-Pad13)") (class "Default")
      (node (ref "U2") (pin "13") (pinfunction "PD7_13") (pintype "bidirectional"))
    )
    (net (code "79") (name "unconnected-(U5-ALERT{slash}RDY-Pad2)") (class "Default")
      (node (ref "U5") (pin "2") (pinfunction "ALERT/RDY_2") (pintype "bidirectional"))
    )
    (net (code "80") (name "unconnected-(U6-ALERT{slash}RDY-Pad2)") (class "Default")
      (node (ref "U6") (pin "2") (pinfunction "ALERT/RDY_2") (pintype "bidirectional"))
    )
  )
)
